# Power.net
KiCad netlist of a schematic drawn in Altium Designer
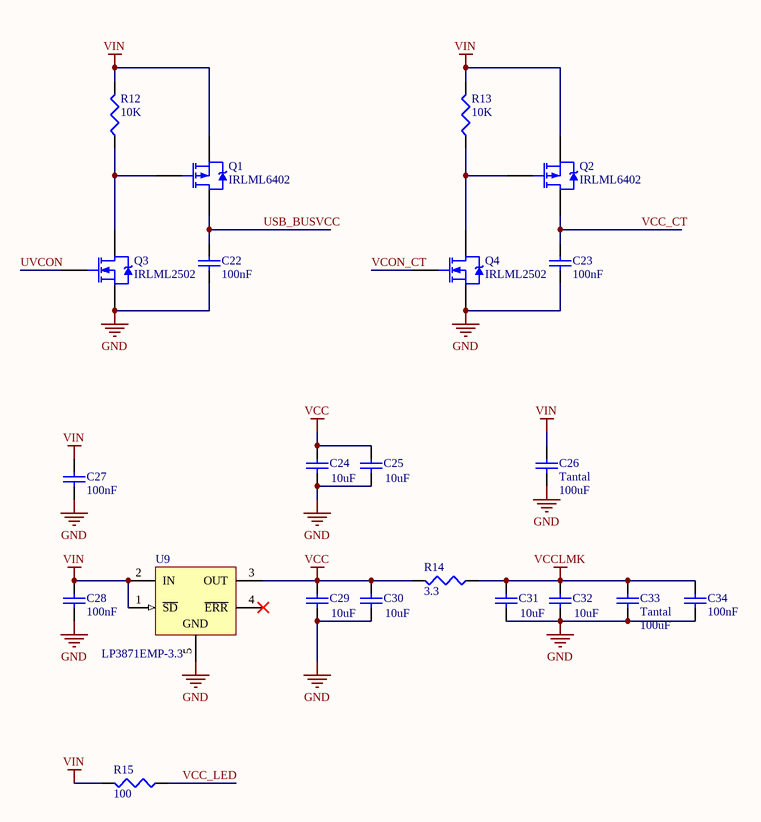
[diagram p0: Power.SchDoc]

(export (version "E")
  (design (tool "Eeschema 10.0.6"))
  (components
    (comp (ref "C22")
      (value "100nF")
      (footprint "1608[0603]")
      (description "Capacitor (Semiconductor SIM Model)")
      (fields (field (name "PUBLISHER") "Altium Limited"))
      (libsource (lib "Miscellaneous Devices") (part "Cap Semi"))
    )
    (comp (ref "C23")
      (value "100nF")
      (footprint "1608[0603]")
      (description "Capacitor (Semiconductor SIM Model)")
      (fields (field (name "PUBLISHER") "Altium Limited"))
      (libsource (lib "Miscellaneous Devices") (part "Cap Semi"))
    )
    (comp (ref "C24")
      (value "10uF")
      (footprint "C1210")
      (description "Capacitor (Semiconductor SIM Model)")
      (fields (field (name "PUBLISHER") "Altium Limited"))
      (libsource (lib "Miscellaneous Devices") (part "Cap Semi"))
    )
    (comp (ref "C25")
      (value "10uF")
      (footprint "C1210")
      (description "Capacitor (Semiconductor SIM Model)")
      (fields (field (name "PUBLISHER") "Altium Limited"))
      (libsource (lib "Miscellaneous Devices") (part "Cap Semi"))
    )
    (comp (ref "C26")
      (value "Tantal")
      (footprint "C2512")
      (description "Capacitor (Semiconductor SIM Model)")
      (fields (field (name "ALTIUM_VALUE") "100uF") (field (name "PUBLISHER") "Altium Limited"))
      (libsource (lib "Miscellaneous Devices") (part "Cap Semi"))
    )
    (comp (ref "C27")
      (value "100nF")
      (footprint "1608[0603]")
      (description "Capacitor (Semiconductor SIM Model)")
      (fields (field (name "PUBLISHER") "Altium Limited"))
      (libsource (lib "Miscellaneous Devices") (part "Cap Semi"))
    )
    (comp (ref "C28")
      (value "100nF")
      (footprint "1608[0603]")
      (description "Capacitor (Semiconductor SIM Model)")
      (fields (field (name "PUBLISHER") "Altium Limited"))
      (libsource (lib "Miscellaneous Devices") (part "Cap Semi"))
    )
    (comp (ref "C29")
      (value "10uF")
      (footprint "C1210")
      (description "Capacitor (Semiconductor SIM Model)")
      (fields (field (name "PUBLISHER") "Altium Limited"))
      (libsource (lib "Miscellaneous Devices") (part "Cap Semi"))
    )
    (comp (ref "C30")
      (value "10uF")
      (footprint "C1210")
      (description "Capacitor (Semiconductor SIM Model)")
      (fields (field (name "PUBLISHER") "Altium Limited"))
      (libsource (lib "Miscellaneous Devices") (part "Cap Semi"))
    )
    (comp (ref "C31")
      (value "10uF")
      (footprint "C1210")
      (description "Capacitor (Semiconductor SIM Model)")
      (fields (field (name "PUBLISHER") "Altium Limited"))
      (libsource (lib "Miscellaneous Devices") (part "Cap Semi"))
    )
    (comp (ref "C32")
      (value "10uF")
      (footprint "C1210")
      (description "Capacitor (Semiconductor SIM Model)")
      (fields (field (name "PUBLISHER") "Altium Limited"))
      (libsource (lib "Miscellaneous Devices") (part "Cap Semi"))
    )
    (comp (ref "C33")
      (value "Tantal")
      (footprint "C2512")
      (description "Capacitor (Semiconductor SIM Model)")
      (fields (field (name "ALTIUM_VALUE") "100uF") (field (name "PUBLISHER") "Altium Limited"))
      (libsource (lib "Miscellaneous Devices") (part "Cap Semi"))
    )
    (comp (ref "C34")
      (value "100nF")
      (footprint "1608[0603]")
      (description "Capacitor (Semiconductor SIM Model)")
      (fields (field (name "PUBLISHER") "Altium Limited"))
      (libsource (lib "Miscellaneous Devices") (part "Cap Semi"))
    )
    (comp (ref "Q1")
      (value "IRLML6402")
      (footprint "SOT-23_N")
      (description "HEXFET Power MOSFET")
      (fields (field (name "PUBLISHER") "Altium Limited"))
      (libsource (lib "IR Discrete MOSFET - Power") (part "IRLML6302"))
    )
    (comp (ref "Q2")
      (value "IRLML6402")
      (footprint "SOT-23_N")
      (description "HEXFET Power MOSFET")
      (fields (field (name "PUBLISHER") "Altium Limited"))
      (libsource (lib "IR Discrete MOSFET - Power") (part "IRLML6302"))
    )
    (comp (ref "Q3")
      (value "IRLML2502")
      (footprint "SOT-23_N")
      (description "HEXFET Power MOSFET")
      (fields (field (name "PUBLISHER") "Altium Limited"))
      (libsource (lib "IR Discrete MOSFET - Power") (part "IRLML2402"))
    )
    (comp (ref "Q4")
      (value "IRLML2502")
      (footprint "SOT-23_N")
      (description "HEXFET Power MOSFET")
      (fields (field (name "PUBLISHER") "Altium Limited"))
      (libsource (lib "IR Discrete MOSFET - Power") (part "IRLML2402"))
    )
    (comp (ref "R12")
      (value "10K")
      (footprint "J1-0603")
      (description "Resistor")
      (fields (field (name "PUBLISHER") "Altium Limited"))
      (libsource (lib "Miscellaneous Devices") (part "Res3"))
    )
    (comp (ref "R13")
      (value "10K")
      (footprint "J1-0603")
      (description "Resistor")
      (fields (field (name "PUBLISHER") "Altium Limited"))
      (libsource (lib "Miscellaneous Devices") (part "Res3"))
    )
    (comp (ref "R14")
      (value "3.3")
      (footprint "J1-0603")
      (description "Resistor")
      (fields (field (name "PUBLISHER") "Altium Limited"))
      (libsource (lib "Miscellaneous Devices") (part "Res3"))
    )
    (comp (ref "R15")
      (value "100")
      (footprint "J1-0603")
      (description "Resistor")
      (fields (field (name "PUBLISHER") "Altium Limited"))
      (libsource (lib "Miscellaneous Devices") (part "Res3"))
    )
    (comp (ref "U9")
      (value "LP3871EMP-3.3")
      (footprint "MP05A_N")
      (description "0.8A Fast Ultra Low Dropout Linear Regulators, 5-pin SOT-223")
      (fields
        (field (name "MANUFACTURER") "National Semiconductor")
        (field (name "PUBLISHER") "Altium Limited")
      )
      (libsource (lib "NSC LDO") (part "LP3871EMP-3.3"))
    )
  )
  (nets
    (net (code "1") (name "/USB_BUSVCC") (class "Default")
      (node (ref "C22") (pin "1") (pinfunction "1_1") (pintype "passive"))
      (node (ref "Q1") (pin "3") (pinfunction "D_3") (pintype "passive"))
    )
    (net (code "2") (name "/UVCON") (class "Default")
      (node (ref "Q3") (pin "1") (pinfunction "G_1") (pintype "passive"))
    )
    (net (code "3") (name "/VCC_CT") (class "Default")
      (node (ref "C23") (pin "1") (pinfunction "1_1") (pintype "passive"))
      (node (ref "Q2") (pin "3") (pinfunction "D_3") (pintype "passive"))
    )
    (net (code "4") (name "/VCC_LED") (class "Default")
      (node (ref "R15") (pin "1") (pinfunction "1_1") (pintype "passive"))
    )
    (net (code "5") (name "/VCON_CT") (class "Default")
      (node (ref "Q4") (pin "1") (pinfunction "G_1") (pintype "passive"))
    )
    (net (code "6") (name "GND") (class "Default")
      (node (ref "C22") (pin "2") (pinfunction "2_2") (pintype "passive"))
      (node (ref "C23") (pin "2") (pinfunction "2_2") (pintype "passive"))
      (node (ref "C24") (pin "1") (pinfunction "1_1") (pintype "passive"))
      (node (ref "C25") (pin "1") (pinfunction "1_1") (pintype "passive"))
      (node (ref "C26") (pin "1") (pinfunction "1_1") (pintype "passive"))
      (node (ref "C27") (pin "2") (pinfunction "2_2") (pintype "passive"))
      (node (ref "C28") (pin "2") (pinfunction "2_2") (pintype "passive"))
      (node (ref "C29") (pin "1") (pinfunction "1_1") (pintype "passive"))
      (node (ref "C30") (pin "1") (pinfunction "1_1") (pintype "passive"))
      (node (ref "C31") (pin "1") (pinfunction "1_1") (pintype "passive"))
      (node (ref "C32") (pin "1") (pinfunction "1_1") (pintype "passive"))
      (node (ref "C33") (pin "1") (pinfunction "1_1") (pintype "passive"))
      (node (ref "C34") (pin "2") (pinfunction "2_2") (pintype "passive"))
      (node (ref "Q3") (pin "2") (pinfunction "S_2") (pintype "passive"))
      (node (ref "Q4") (pin "2") (pinfunction "S_2") (pintype "passive"))
      (node (ref "U9") (pin "5") (pinfunction "GND_5") (pintype "power_in"))
    )
    (net (code "7") (name "Net-(Q1-G)") (class "Default")
      (node (ref "Q1") (pin "1") (pinfunction "G_1") (pintype "passive"))
      (node (ref "Q3") (pin "3") (pinfunction "D_3") (pintype "passive"))
      (node (ref "R12") (pin "1") (pinfunction "1_1") (pintype "passive"))
    )
    (net (code "8") (name "Net-(Q2-G)") (class "Default")
      (node (ref "Q2") (pin "1") (pinfunction "G_1") (pintype "passive"))
      (node (ref "Q4") (pin "3") (pinfunction "D_3") (pintype "passive"))
      (node (ref "R13") (pin "1") (pinfunction "1_1") (pintype "passive"))
    )
    (net (code "9") (name "VCC") (class "Default")
      (node (ref "C24") (pin "2") (pinfunction "2_2") (pintype "passive"))
      (node (ref "C25") (pin "2") (pinfunction "2_2") (pintype "passive"))
      (node (ref "C29") (pin "2") (pinfunction "2_2") (pintype "passive"))
      (node (ref "C30") (pin "2") (pinfunction "2_2") (pintype "passive"))
      (node (ref "R14") (pin "2") (pinfunction "2_2") (pintype "passive"))
      (node (ref "U9") (pin "3") (pinfunction "OUT_3") (pintype "power_in"))
    )
    (net (code "10") (name "VCCLMK") (class "Default")
      (node (ref "C31") (pin "2") (pinfunction "2_2") (pintype "passive"))
      (node (ref "C32") (pin "2") (pinfunction "2_2") (pintype "passive"))
      (node (ref "C33") (pin "2") (pinfunction "2_2") (pintype "passive"))
      (node (ref "C34") (pin "1") (pinfunction "1_1") (pintype "passive"))
      (node (ref "R14") (pin "1") (pinfunction "1_1") (pintype "passive"))
    )
    (net (code "11") (name "VIN") (class "Default")
      (node (ref "C26") (pin "2") (pinfunction "2_2") (pintype "passive"))
      (node (ref "C27") (pin "1") (pinfunction "1_1") (pintype "passive"))
      (node (ref "C28") (pin "1") (pinfunction "1_1") (pintype "passive"))
      (node (ref "Q1") (pin "2") (pinfunction "S_2") (pintype "passive"))
      (node (ref "Q2") (pin "2") (pinfunction "S_2") (pintype "passive"))
      (node (ref "R12") (pin "2") (pinfunction "2_2") (pintype "passive"))
      (node (ref "R13") (pin "2") (pinfunction "2_2") (pintype "passive"))
      (node (ref "R15") (pin "2") (pinfunction "2_2") (pintype "passive"))
      (node (ref "U9") (pin "1") (pinfunction "~{SD}_1") (pintype "input"))
      (node (ref "U9") (pin "2") (pinfunction "IN_2") (pintype "power_in"))
    )
    (net (code "12") (name "unconnected-(U9-~{ERR}-Pad4)") (class "Default")
      (node (ref "U9") (pin "4") (pinfunction "~{ERR}_4") (pintype "open_collector+no_connect"))
    )
  )
)
